# PoE_Si3404.net
KiCad netlist of a schematic drawn in Altium Designer
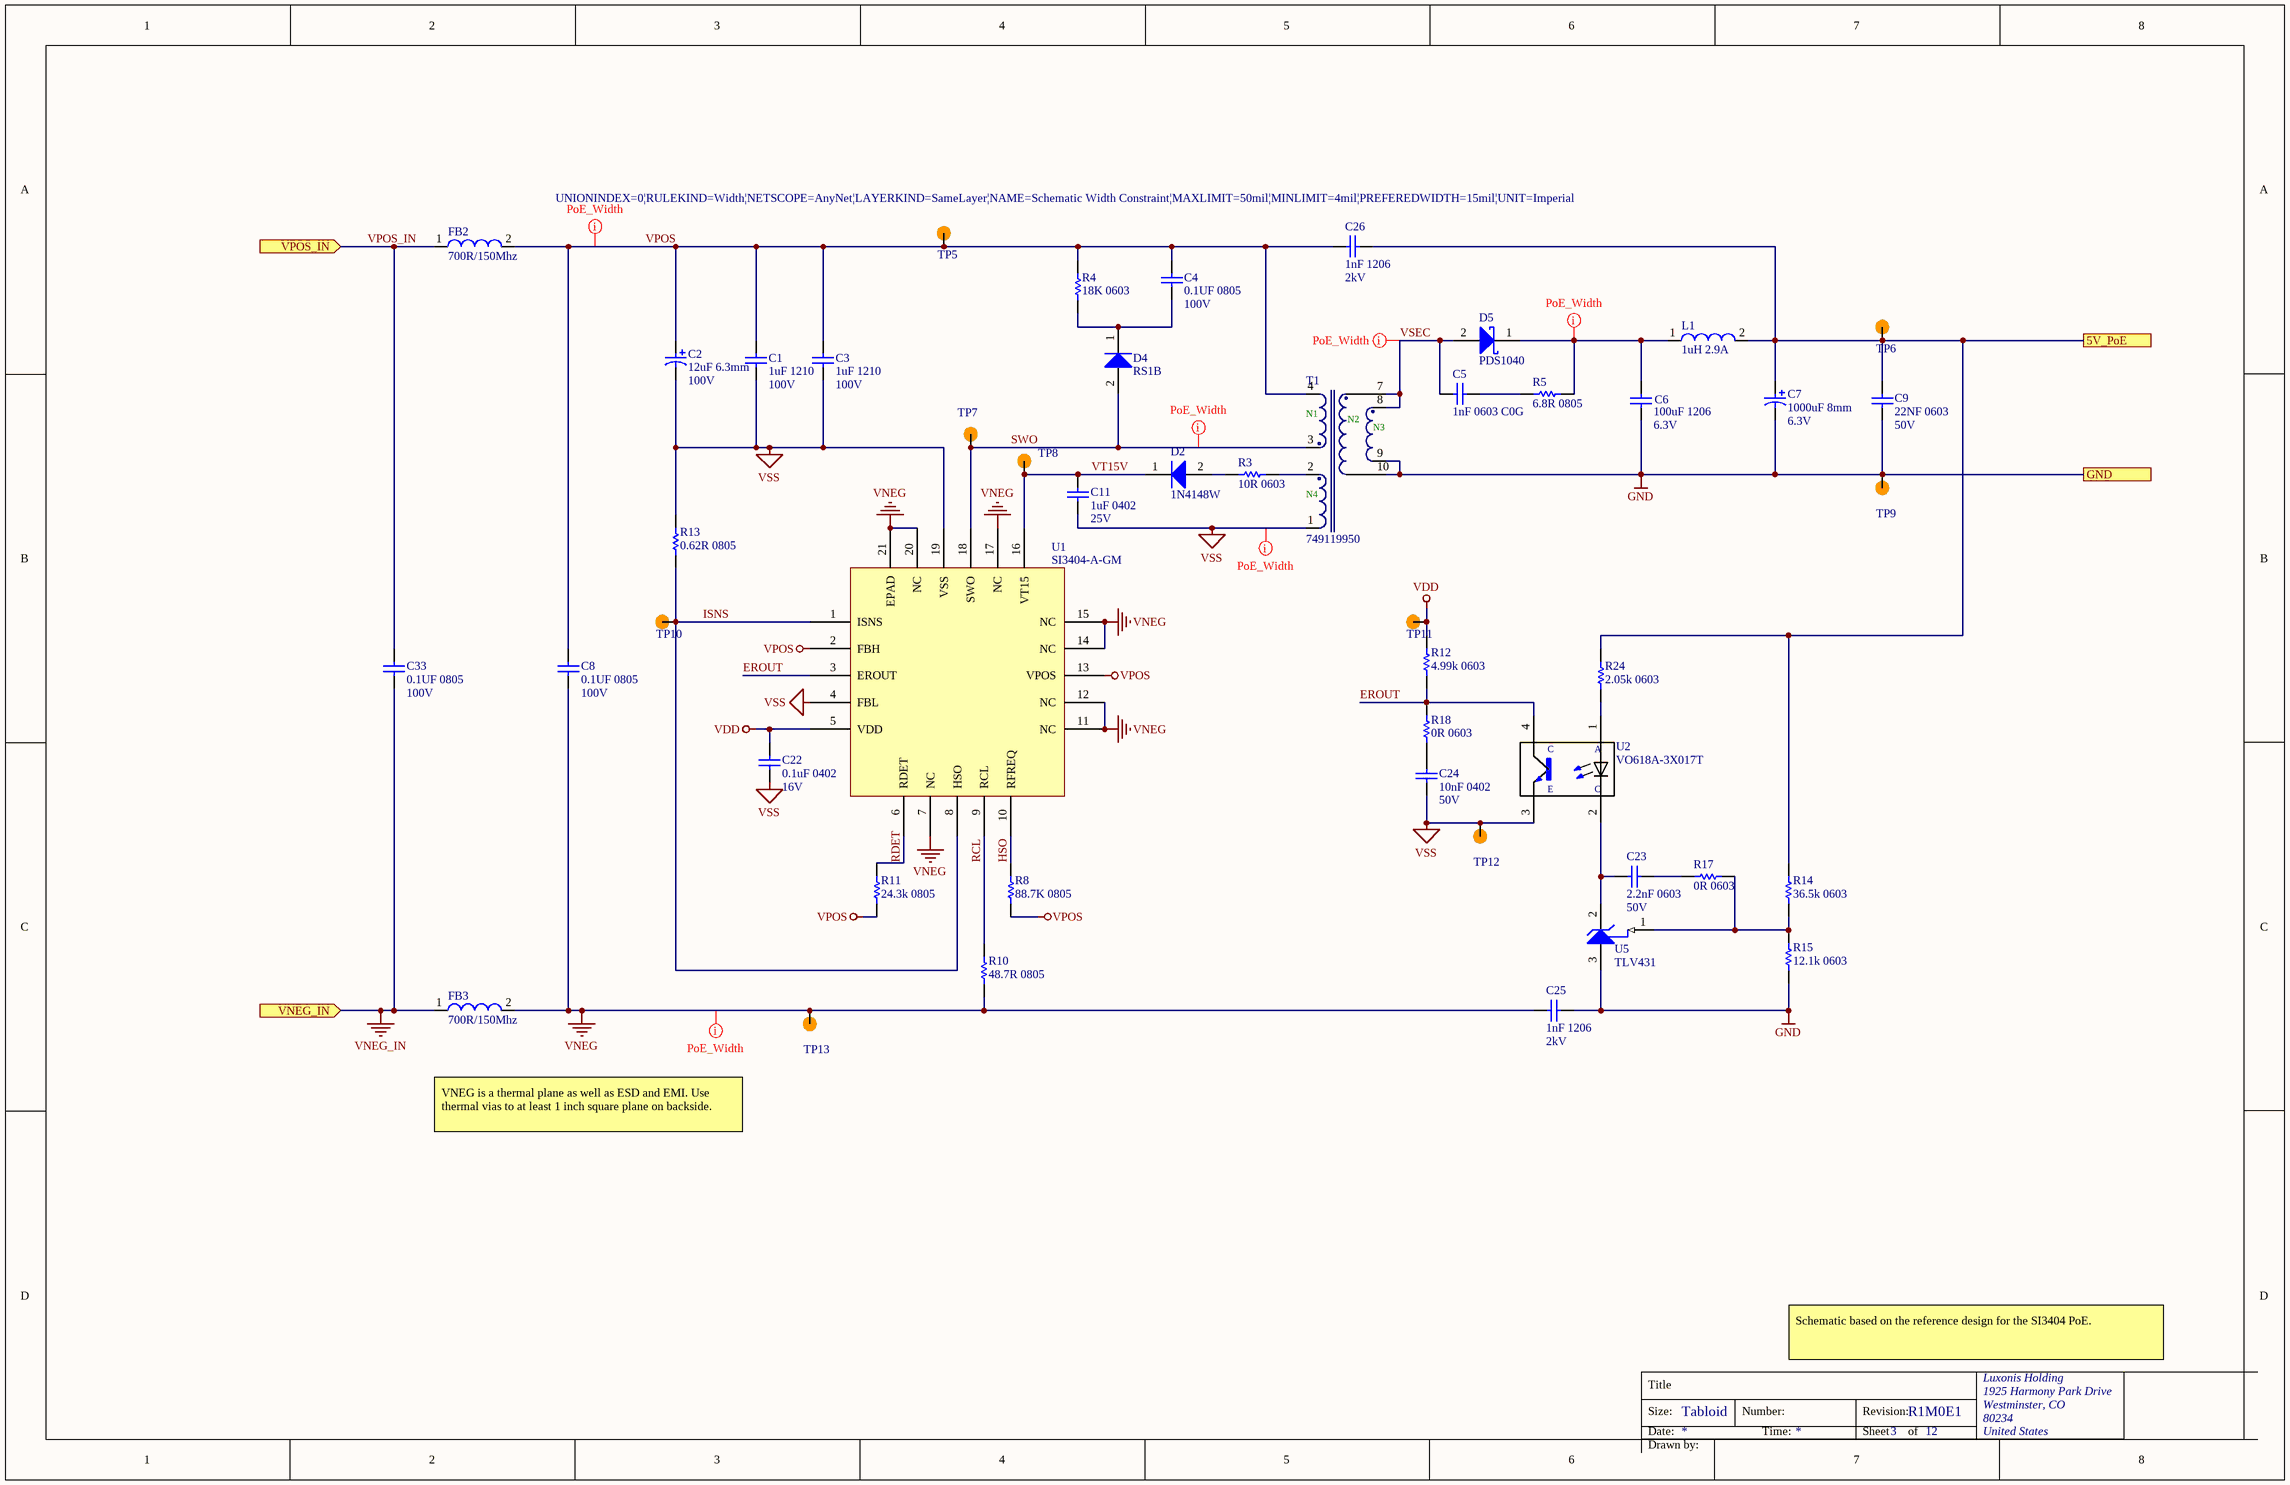
[diagram p0: PoE_Si3404.SchDoc]

(export (version "E")
  (design (tool "Eeschema 10.0.6"))
  (components
    (comp (ref "C1")
      (value "1uF 1210")
      (footprint "CAP_Altium_Vault_Generic:CAPC1210(3225)280_N")
      (description "CAP CER 1UF 100V X7R 1210")
      (fields (field (name "TOLERANCE") "10%") (field (name "VOLTAGE RATING") "100V"))
      (libsource (lib "PCBProject") (part "CL32B105KCJNNNE"))
    )
    (comp (ref "C2")
      (value "12uF 6.3mm")
      (footprint "BW2098POE:EEU-FC2A120")
      (description "CAP ALUM 12UF 20% 100V RADIAL")
      (fields (field (name "TOLERANCE") "20%") (field (name "VOLTAGE") "100V"))
      (libsource (lib "BW2098POE") (part "EEU-FC2A120"))
    )
    (comp (ref "C3")
      (value "1uF 1210")
      (footprint "CAP_Altium_Vault_Generic:CAPC1210(3225)280_N")
      (description "CAP CER 1UF 100V X7R 1210")
      (fields (field (name "TOLERANCE") "10%") (field (name "VOLTAGE RATING") "100V"))
      (libsource (lib "PCBProject") (part "CL32B105KCJNNNE"))
    )
    (comp (ref "C4")
      (value "0.1UF 0805")
      (footprint "CAP_Altium_Vault_Generic:CAPC0805(2012)145_N")
      (description "CAP CER 0.1UF 100V X7R 0805")
      (fields (field (name "TOLERANCE") "10%") (field (name "VOLTAGE RATING") "100V"))
      (libsource (lib "BW2098POE") (part "CL21B104KCFNNNE"))
    )
    (comp (ref "C5")
      (value "1nF 0603 C0G")
      (footprint "CAP_Altium_Vault_Generic:CAPC0603(1608)100_N")
      (description "CAP CER 1000PF 50V C0G/NP0 0603")
      (fields
        (field (name "MANUFACTURER") "Murata")
        (field (name "MANUFACTURER PART NUMBER") "GRM1885C1H102FA01D")
      )
      (libsource (lib "LuxonisMaster") (part "GRM1885C1H102FA01D"))
    )
    (comp (ref "C6")
      (value "100uF 1206")
      (footprint "CAP_Altium_Vault_Generic:CAPC1206(3216)190_N")
      (description "CAP CER 100UF 6.3V X5R 1206")
      (fields (field (name "TOLERANCE") "20%") (field (name "VOLTAGE") "6.3V"))
      (libsource (lib "PCBProject") (part "CL31A107MQHNNNE"))
    )
    (comp (ref "C7")
      (value "1000uF 8mm")
      (footprint "ECA-0JM102")
      (description "CAP ALUM 1000UF 20% 6.3V RADIAL")
      (fields (field (name "TOLERANCE") "20%") (field (name "VOLTAGE") "6.3V"))
      (libsource (lib "MB2096POE") (part "ECA-0JM102"))
    )
    (comp (ref "C8")
      (value "0.1UF 0805")
      (footprint "CAP_Altium_Vault_Generic:CAPC0805(2012)145_N")
      (description "CAP CER 0.1UF 100V X7R 0805")
      (fields (field (name "TOLERANCE") "10%") (field (name "VOLTAGE RATING") "100V"))
      (libsource (lib "PCBProject") (part "CL21B104KCFNNNE"))
    )
    (comp (ref "C9")
      (value "22NF 0603")
      (footprint "CAP_Altium_Vault_Generic:CAPC0603(1608)100_N")
      (description "CAP CER 0.022UF 50V X7R 0603")
      (fields (field (name "TOLERANCE") "10%") (field (name "VOLTAGE") "50V"))
      (libsource (lib "LuxonisMaster") (part "C0603C223K5RACTU"))
    )
    (comp (ref "C11")
      (value "1uF 0402")
      (footprint "CAP_Altium_Vault_Generic:CAPC0402(1005)70_N")
      (description "CAP CER 1UF 25V X5R 0402 10%")
      (fields
        (field (name "TOLERANCE") "10%")
        (field (name "VOLTAGE") "25V")
        (field (name "VOLTAGE RATING") "25V")
      )
      (libsource (lib "LuxonisMaster") (part "GRM155R61E105KA12D"))
    )
    (comp (ref "C22")
      (value "0.1uF 0402")
      (footprint "CAP_Altium_Vault_Generic:CAPC0402(1005)60_N")
      (description "CAP CER 0.1UF 16V X7R 0402")
      (fields (field (name "TOLERANCE") "10%") (field (name "VOLTAGE RATING") "16V"))
      (libsource (lib "PCBProject") (part "CL05B104KO5NFNC"))
    )
    (comp (ref "C23")
      (value "2.2nF 0603")
      (footprint "CAP_Altium_Vault_Generic:CAPC0603(1608)100_N")
      (description "CAP CER 2200PF 50V C0G/NP0 0603")
      (fields (field (name "TOLERANCE") "5%") (field (name "VOLTAGE") "50V"))
      (libsource (lib "BW2098POE") (part "GRM1885C1H222JA01D"))
    )
    (comp (ref "C24")
      (value "10nF 0402")
      (footprint "CAP_Altium_Vault_Generic:CAPC0402(1005)60_N")
      (description "CAP CER 10000PF 50V X7R 0402")
      (fields
        (field (name "TOLERANCE") "10%")
        (field (name "VOLTAGE") "25V")
        (field (name "VOLTAGE RATING") "50V")
      )
      (libsource (lib "LuxonisMaster") (part "GRM155R71H103KA88D"))
    )
    (comp (ref "C25")
      (value "1nF 1206")
      (footprint "CAP_Altium_Vault_Generic:CAPC1206(3216)190_N")
      (description "CAP CER 1000PF 2KV X7R 1206")
      (fields (field (name "TOLERANCE") "10%") (field (name "VOLTAGE RATING (DC)") "2kV"))
      (libsource (lib "PCBProject") (part "C1206C102KGRACTU"))
    )
    (comp (ref "C26")
      (value "1nF 1206")
      (footprint "CAP_Altium_Vault_Generic:CAPC1206(3216)190_N")
      (description "CAP CER 1000PF 2KV X7R 1206")
      (fields (field (name "TOLERANCE") "10%") (field (name "VOLTAGE RATING (DC)") "2kV"))
      (libsource (lib "PCBProject") (part "C1206C102KGRACTU"))
    )
    (comp (ref "C33")
      (value "0.1UF 0805")
      (footprint "CAP_Altium_Vault_Generic:CAPC0805(2012)145_N")
      (description "CAP CER 0.1UF 100V X7R 0805")
      (fields (field (name "TOLERANCE") "10%") (field (name "VOLTAGE RATING") "100V"))
      (libsource (lib "PCBProject") (part "CL21B104KCFNNNE"))
    )
    (comp (ref "D2")
      (value "1N4148W")
      (footprint "BW2098POE:1N4148W-7-F")
      (description "DIODE GEN PURP 100V 300MA SOD123")
      (fields (field (name "VOLTAGE") "100V"))
      (libsource (lib "PCBProject") (part "1N4148W-7-F"))
    )
    (comp (ref "D4")
      (value "RS1B")
      (footprint "BW2098POE:RS1B")
      (description "DIODE GEN PURP 100V 1A SMA")
      (libsource (lib "BW2098POE") (part "RS1B"))
    )
    (comp (ref "D5")
      (value "PDS1040")
      (footprint "BW2098POE:PDS1040-13")
      (description "DIODE SCHOTTKY 40V 10A POWERDI5")
      (libsource (lib "PCBProject") (part "PDS1040-13"))
    )
    (comp (ref "FB2")
      (value "700R/150Mhz")
      (footprint "BW2098POE:742792040")
      (description "FERRITE BEAD 600 OHM 0805 1LN")
      (fields (field (name "TOLERANCE") "25%"))
      (libsource (lib "BW2098POE") (part "742792040"))
    )
    (comp (ref "FB3")
      (value "700R/150Mhz")
      (footprint "BW2098POE:742792040")
      (description "FERRITE BEAD 600 OHM 0805 1LN")
      (fields (field (name "TOLERANCE") "25%"))
      (libsource (lib "BW2098POE") (part "742792040"))
    )
    (comp (ref "L1")
      (value "1uH 2.9A")
      (footprint "BW2098POE:DO1608C-102MLx")
      (description "IND POWER WIREWOUND 1uH 20% 100KHz FERRITE 2.7A")
      (fields (field (name "TOLERANCE") "20%"))
      (libsource (lib "PCBProject") (part "DO1608C-102ML"))
    )
    (comp (ref "R3")
      (value "10R 0603")
      (footprint "RES_Altium_Vault_Generic:RESC0603(1608)_N")
      (description "RES SMD 10 OHM 1% 1/10W 0603")
      (fields (field (name "TOLERANCE") "1%"))
      (libsource (lib "PCBProject") (part "CRCW060310R0FKEA"))
    )
    (comp (ref "R4")
      (value "18K 0603")
      (footprint "RES_Altium_Vault_Generic:RESC0603(1608)_N")
      (description "RES SMD 18K OHM 5% 1/10W 0603")
      (fields (field (name "TOLERANCE") "5%"))
      (libsource (lib "BW2098POE") (part "RC0603JR-0718KL"))
    )
    (comp (ref "R5")
      (value "6.8R 0805")
      (footprint "RES_Altium_Vault_Generic:RESC0805(2012)_N")
      (description "RES SMD 6.8 OHM 1% 1/8W 0805")
      (fields (field (name "TOLERANCE") "1%"))
      (libsource (lib "BW2098POE") (part "RC0805FR-076R8L"))
    )
    (comp (ref "R8")
      (value "88.7K 0805")
      (footprint "RES_Altium_Vault_Generic:RESC0805(2012)_N")
      (description "RES SMD 88.7K OHM 1% 1/8W 0805")
      (fields (field (name "TOLERANCE") "1%"))
      (libsource (lib "BW2098POE") (part "CRCW080588K7FKEA"))
    )
    (comp (ref "R10")
      (value "48.7R 0805")
      (footprint "RES_Altium_Vault_Generic:RESC0805(2012)_N")
      (description "RES SMD 48.7 OHM 1% 1/8W 0805")
      (fields (field (name "TOLERANCE") "1%"))
      (libsource (lib "PCBProject") (part "RC0805FR-0748R7L"))
    )
    (comp (ref "R11")
      (value "24.3k 0805")
      (footprint "RES_Altium_Vault_Generic:RESC0805(2012)_N")
      (description "RES SMD 24.3K OHM 1% 1/8W 0805")
      (fields (field (name "TOLERANCE") "1%"))
      (libsource (lib "PCBProject") (part "CRCW080524K3FKEA"))
    )
    (comp (ref "R12")
      (value "4.99k 0603")
      (footprint "RES_Altium_Vault_Generic:RESC0603(1608)_N")
      (description "RES SMD 4.99K OHM 1% 1/10W 0603")
      (fields (field (name "TOLERANCE") "1%"))
      (libsource (lib "PCBProject") (part "RC0603FR-074K99L"))
    )
    (comp (ref "R13")
      (value "0.62R 0805")
      (footprint "RES_Altium_Vault_Generic:RESC0805(2012)_N")
      (description "RES SMD 620 MOHM 1% 1/8W 0805")
      (fields (field (name "TOLERANCE") "1%"))
      (libsource (lib "BW2098POE") (part "RL0805FR-070R62L"))
    )
    (comp (ref "R14")
      (value "36.5k 0603")
      (footprint "RES_Altium_Vault_Generic:RESC0603(1608)_N")
      (description "RES SMD 36.5K OHM 1% 1/10W 0603")
      (fields (field (name "TOLERANCE") "1%"))
      (libsource (lib "PCBProject") (part "RC0603FR-0736K5L"))
    )
    (comp (ref "R15")
      (value "12.1k 0603")
      (footprint "RES_Altium_Vault_Generic:RESC0603(1608)_N")
      (description "RES SMD 12.1K OHM 1% 1/10W 0603")
      (fields (field (name "TOLERANCE") "1%"))
      (libsource (lib "PCBProject") (part "RC0603FR-0712K1L"))
    )
    (comp (ref "R17")
      (value "0R 0603")
      (footprint "RES_Altium_Vault_Generic:RESC0603(1608)_N")
      (fields (field (name "TOLERANCE") "5%"))
      (libsource (lib "LuxonisMaster") (part "CRCW06030000Z0EA"))
    )
    (comp (ref "R18")
      (value "0R 0603")
      (footprint "RES_Altium_Vault_Generic:RESC0603(1608)_N")
      (fields (field (name "TOLERANCE") "5%"))
      (libsource (lib "LuxonisMaster") (part "CRCW06030000Z0EA"))
    )
    (comp (ref "R24")
      (value "2.05k 0603")
      (footprint "RES_Altium_Vault_Generic:RESC0603(1608)_N")
      (description "RES SMD 2.05K OHM 1% 1/10W 0603")
      (fields (field (name "TOLERANCE") "1%"))
      (libsource (lib "PCBProject") (part "RC0603FR-072K05L"))
    )
    (comp (ref "T1")
      (value "749119950")
      (footprint "BW2098POE:749119950")
      (description "TRANS FLYBACK POE 127UH SMD")
      (libsource (lib "BW2098POE") (part "749119950"))
    )
    (comp (ref "TP5")
      (value "TP100_200_NS")
      (footprint "LuxonisMaster:TP100_200_NS")
      (libsource (lib "LuxonisMaster") (part "TEST_POINT"))
    )
    (comp (ref "TP6")
      (value "TP100_200_NS")
      (footprint "LuxonisMaster:TP100_200_NS")
      (libsource (lib "LuxonisMaster") (part "TEST_POINT"))
    )
    (comp (ref "TP7")
      (value "TP100_200_NS")
      (footprint "LuxonisMaster:TP100_200_NS")
      (libsource (lib "LuxonisMaster") (part "TEST_POINT"))
    )
    (comp (ref "TP8")
      (value "TP100_200_NS")
      (footprint "LuxonisMaster:TP100_200_NS")
      (libsource (lib "LuxonisMaster") (part "TEST_POINT"))
    )
    (comp (ref "TP9")
      (value "TP100_200_NS")
      (footprint "LuxonisMaster:TP100_200_NS")
      (libsource (lib "LuxonisMaster") (part "TEST_POINT"))
    )
    (comp (ref "TP10")
      (value "TP100_200_NS")
      (footprint "LuxonisMaster:TP100_200_NS")
      (libsource (lib "LuxonisMaster") (part "TEST_POINT"))
    )
    (comp (ref "TP11")
      (value "TP100_200_NS")
      (footprint "LuxonisMaster:TP100_200_NS")
      (libsource (lib "LuxonisMaster") (part "TEST_POINT"))
    )
    (comp (ref "TP12")
      (value "TP100_200_NS")
      (footprint "LuxonisMaster:TP100_200_NS")
      (libsource (lib "LuxonisMaster") (part "TEST_POINT"))
    )
    (comp (ref "TP13")
      (value "TP100_200_NS")
      (footprint "LuxonisMaster:TP100_200_NS")
      (libsource (lib "LuxonisMaster") (part "TEST_POINT"))
    )
    (comp (ref "U1")
      (value "SI3404-A-GM")
      (footprint "BW2098POE:Si3404-A-GM")
      (description "IC POE CNTRL 1 CHANNEL 20QFN")
      (libsource (lib "BW2098POE") (part "SI3404-A-GM"))
    )
    (comp (ref "U2")
      (value "VO618A-3X017T")
      (footprint "BW2098POE:VO618A-3X017T")
      (description "OPTOISOLATOR 5.3KV TRANS 4-SMD")
      (libsource (lib "BW2098POE") (part "VO618A-3X017T"))
    )
    (comp (ref "U5")
      (value "TLV431")
      (footprint "BW2098POE:TLV431BCDBZR")
      (description "IC VREF SHUNT ADJ SOT23-3")
      (fields (field (name "TOLERANCE") "0.5%"))
      (libsource (lib "BW2098POE") (part "TLV431BCDBZR"))
    )
  )
  (nets
    (net (code "1") (name "/5V_PoE") (class "Default")
      (node (ref "C26") (pin "2") (pinfunction "2_2") (pintype "passive"))
      (node (ref "C7") (pin "1") (pinfunction "1_1") (pintype "passive"))
      (node (ref "C9") (pin "2") (pinfunction "2_2") (pintype "passive"))
      (node (ref "L1") (pin "2") (pinfunction "2_2") (pintype "passive"))
      (node (ref "R14") (pin "2") (pinfunction "2_2") (pintype "passive"))
      (node (ref "R24") (pin "2") (pinfunction "2_2") (pintype "passive"))
      (node (ref "TP6") (pin "1") (pintype "passive"))
    )
    (net (code "2") (name "/EROUT") (class "Default")
      (node (ref "R12") (pin "1") (pinfunction "1_1") (pintype "passive"))
      (node (ref "R18") (pin "2") (pinfunction "2_2") (pintype "passive"))
      (node (ref "U1") (pin "3") (pinfunction "EROUT_3") (pintype "passive"))
      (node (ref "U2") (pin "4") (pinfunction "CO_4") (pintype "passive"))
    )
    (net (code "3") (name "/HSO") (class "Default")
      (node (ref "R8") (pin "2") (pinfunction "2_2") (pintype "passive"))
      (node (ref "U1") (pin "10") (pinfunction "RFREQ_10") (pintype "passive"))
    )
    (net (code "4") (name "/ISNS") (class "Default")
      (node (ref "R13") (pin "1") (pinfunction "1_1") (pintype "passive"))
      (node (ref "TP10") (pin "1") (pintype "passive"))
      (node (ref "U1") (pin "1") (pinfunction "ISNS_1") (pintype "passive"))
      (node (ref "U1") (pin "8") (pinfunction "HSO_8") (pintype "passive"))
    )
    (net (code "5") (name "/RCL") (class "Default")
      (node (ref "R10") (pin "2") (pinfunction "2_2") (pintype "passive"))
      (node (ref "U1") (pin "9") (pinfunction "RCL_9") (pintype "passive"))
    )
    (net (code "6") (name "/RDET") (class "Default")
      (node (ref "R11") (pin "2") (pinfunction "2_2") (pintype "passive"))
      (node (ref "U1") (pin "6") (pinfunction "RDET_6") (pintype "passive"))
    )
    (net (code "7") (name "/SWO") (class "Default")
      (node (ref "D4") (pin "2") (pinfunction "A_2") (pintype "passive"))
      (node (ref "T1") (pin "3") (pinfunction "3_3") (pintype "passive"))
      (node (ref "TP7") (pin "1") (pintype "passive"))
      (node (ref "U1") (pin "18") (pinfunction "SWO_18") (pintype "passive"))
    )
    (net (code "8") (name "/VPOS_IN") (class "Default")
      (node (ref "C33") (pin "2") (pinfunction "2_2") (pintype "passive"))
      (node (ref "FB2") (pin "1") (pinfunction "1_1") (pintype "passive"))
    )
    (net (code "9") (name "/VSEC") (class "Default")
      (node (ref "C5") (pin "2") (pinfunction "2_2") (pintype "passive"))
      (node (ref "D5") (pin "2") (pinfunction "A_2") (pintype "passive"))
      (node (ref "T1") (pin "7") (pinfunction "7_7") (pintype "passive"))
      (node (ref "T1") (pin "8") (pinfunction "8_8") (pintype "passive"))
    )
    (net (code "10") (name "/VT15V") (class "Default")
      (node (ref "C11") (pin "2") (pinfunction "2_2") (pintype "passive"))
      (node (ref "D2") (pin "1") (pinfunction "K_1") (pintype "passive"))
      (node (ref "TP8") (pin "1") (pintype "passive"))
      (node (ref "U1") (pin "16") (pinfunction "VT15_16") (pintype "passive"))
    )
    (net (code "11") (name "GND") (class "Default")
      (node (ref "C25") (pin "2") (pinfunction "2_2") (pintype "passive"))
      (node (ref "C6") (pin "1") (pinfunction "1_1") (pintype "passive"))
      (node (ref "C7") (pin "2") (pinfunction "2_2") (pintype "passive"))
      (node (ref "C9") (pin "1") (pinfunction "1_1") (pintype "passive"))
      (node (ref "R15") (pin "1") (pinfunction "1_1") (pintype "passive"))
      (node (ref "T1") (pin "10") (pinfunction "10_10") (pintype "passive"))
      (node (ref "T1") (pin "9") (pinfunction "9_9") (pintype "passive"))
      (node (ref "TP9") (pin "1") (pintype "passive"))
      (node (ref "U5") (pin "3") (pinfunction "ANODE_3") (pintype "passive"))
    )
    (net (code "12") (name "Net-(C5-Pad1)") (class "Default")
      (node (ref "C5") (pin "1") (pinfunction "1_1") (pintype "passive"))
      (node (ref "R5") (pin "1") (pinfunction "1_1") (pintype "passive"))
    )
    (net (code "13") (name "Net-(C23-Pad2)") (class "Default")
      (node (ref "C23") (pin "2") (pinfunction "2_2") (pintype "passive"))
      (node (ref "R17") (pin "2") (pinfunction "2_2") (pintype "passive"))
    )
    (net (code "14") (name "Net-(C24-Pad2)") (class "Default")
      (node (ref "C24") (pin "2") (pinfunction "2_2") (pintype "passive"))
      (node (ref "R18") (pin "1") (pinfunction "1_1") (pintype "passive"))
    )
    (net (code "15") (name "Net-(D2-A)") (class "Default")
      (node (ref "D2") (pin "2") (pinfunction "A_2") (pintype "passive"))
      (node (ref "R3") (pin "1") (pinfunction "1_1") (pintype "passive"))
    )
    (net (code "16") (name "Net-(D4-K)") (class "Default")
      (node (ref "C4") (pin "1") (pinfunction "1_1") (pintype "passive"))
      (node (ref "D4") (pin "1") (pinfunction "K_1") (pintype "passive"))
      (node (ref "R4") (pin "1") (pinfunction "1_1") (pintype "passive"))
    )
    (net (code "17") (name "Net-(D5-K)") (class "Default")
      (node (ref "C6") (pin "2") (pinfunction "2_2") (pintype "passive"))
      (node (ref "D5") (pin "1") (pinfunction "K_1") (pintype "passive"))
      (node (ref "L1") (pin "1") (pinfunction "1_1") (pintype "passive"))
      (node (ref "R5") (pin "2") (pinfunction "2_2") (pintype "passive"))
    )
    (net (code "18") (name "Net-(R3-Pad2)") (class "Default")
      (node (ref "R3") (pin "2") (pinfunction "2_2") (pintype "passive"))
      (node (ref "T1") (pin "2") (pinfunction "2_2") (pintype "passive"))
    )
    (net (code "19") (name "Net-(U2-A)") (class "Default")
      (node (ref "R24") (pin "1") (pinfunction "1_1") (pintype "passive"))
      (node (ref "U2") (pin "1") (pinfunction "A_1") (pintype "passive"))
    )
    (net (code "20") (name "Net-(U2-C)") (class "Default")
      (node (ref "C23") (pin "1") (pinfunction "1_1") (pintype "passive"))
      (node (ref "U2") (pin "2") (pinfunction "C_2") (pintype "passive"))
      (node (ref "U5") (pin "2") (pinfunction "CATHODE_2") (pintype "passive"))
    )
    (net (code "21") (name "Net-(U5-REF)") (class "Default")
      (node (ref "R14") (pin "1") (pinfunction "1_1") (pintype "passive"))
      (node (ref "R15") (pin "2") (pinfunction "2_2") (pintype "passive"))
      (node (ref "R17") (pin "1") (pinfunction "1_1") (pintype "passive"))
      (node (ref "U5") (pin "1") (pinfunction "REF_1") (pintype "input"))
    )
    (net (code "22") (name "VDD") (class "Default")
      (node (ref "C22") (pin "2") (pinfunction "2_2") (pintype "passive"))
      (node (ref "R12") (pin "2") (pinfunction "2_2") (pintype "passive"))
      (node (ref "TP11") (pin "1") (pintype "passive"))
      (node (ref "U1") (pin "5") (pinfunction "VDD_5") (pintype "passive"))
    )
    (net (code "23") (name "VNEG") (class "Default")
      (node (ref "C25") (pin "1") (pinfunction "1_1") (pintype "passive"))
      (node (ref "C8") (pin "1") (pinfunction "1_1") (pintype "passive"))
      (node (ref "FB3") (pin "2") (pinfunction "2_2") (pintype "passive"))
      (node (ref "R10") (pin "1") (pinfunction "1_1") (pintype "passive"))
      (node (ref "TP13") (pin "1") (pintype "passive"))
      (node (ref "U1") (pin "11") (pinfunction "NC_11") (pintype "passive"))
      (node (ref "U1") (pin "12") (pinfunction "NC_12") (pintype "passive"))
      (node (ref "U1") (pin "14") (pinfunction "NC_14") (pintype "passive"))
      (node (ref "U1") (pin "15") (pinfunction "NC_15") (pintype "passive"))
      (node (ref "U1") (pin "17") (pinfunction "NC_17") (pintype "passive"))
      (node (ref "U1") (pin "20") (pinfunction "NC_20") (pintype "passive"))
      (node (ref "U1") (pin "21") (pinfunction "EPAD_21") (pintype "passive"))
      (node (ref "U1") (pin "7") (pinfunction "NC_7") (pintype "passive"))
    )
    (net (code "24") (name "VNEG_IN") (class "Default")
      (node (ref "C33") (pin "1") (pinfunction "1_1") (pintype "passive"))
      (node (ref "FB3") (pin "1") (pinfunction "1_1") (pintype "passive"))
    )
    (net (code "25") (name "VPOS") (class "Default")
      (node (ref "C1") (pin "2") (pinfunction "2_2") (pintype "passive"))
      (node (ref "C2") (pin "1") (pinfunction "1_1") (pintype "passive"))
      (node (ref "C26") (pin "1") (pinfunction "1_1") (pintype "passive"))
      (node (ref "C3") (pin "2") (pinfunction "2_2") (pintype "passive"))
      (node (ref "C4") (pin "2") (pinfunction "2_2") (pintype "passive"))
      (node (ref "C8") (pin "2") (pinfunction "2_2") (pintype "passive"))
      (node (ref "FB2") (pin "2") (pinfunction "2_2") (pintype "passive"))
      (node (ref "R11") (pin "1") (pinfunction "1_1") (pintype "passive"))
      (node (ref "R4") (pin "2") (pinfunction "2_2") (pintype "passive"))
      (node (ref "R8") (pin "1") (pinfunction "1_1") (pintype "passive"))
      (node (ref "T1") (pin "4") (pinfunction "4_4") (pintype "passive"))
      (node (ref "TP5") (pin "1") (pintype "passive"))
      (node (ref "U1") (pin "13") (pinfunction "VPOS_13") (pintype "passive"))
      (node (ref "U1") (pin "2") (pinfunction "FBH_2") (pintype "passive"))
    )
    (net (code "26") (name "VSS") (class "Default")
      (node (ref "C1") (pin "1") (pinfunction "1_1") (pintype "passive"))
      (node (ref "C11") (pin "1") (pinfunction "1_1") (pintype "passive"))
      (node (ref "C2") (pin "2") (pinfunction "2_2") (pintype "passive"))
      (node (ref "C22") (pin "1") (pinfunction "1_1") (pintype "passive"))
      (node (ref "C24") (pin "1") (pinfunction "1_1") (pintype "passive"))
      (node (ref "C3") (pin "1") (pinfunction "1_1") (pintype "passive"))
      (node (ref "R13") (pin "2") (pinfunction "2_2") (pintype "passive"))
      (node (ref "T1") (pin "1") (pinfunction "1_1") (pintype "passive"))
      (node (ref "TP12") (pin "1") (pintype "passive"))
      (node (ref "U1") (pin "19") (pinfunction "VSS_19") (pintype "passive"))
      (node (ref "U1") (pin "4") (pinfunction "FBL_4") (pintype "passive"))
      (node (ref "U2") (pin "3") (pinfunction "E_3") (pintype "passive"))
    )
  )
)
